# CC2530.net
KiCad netlist of a schematic drawn in Altium Designer
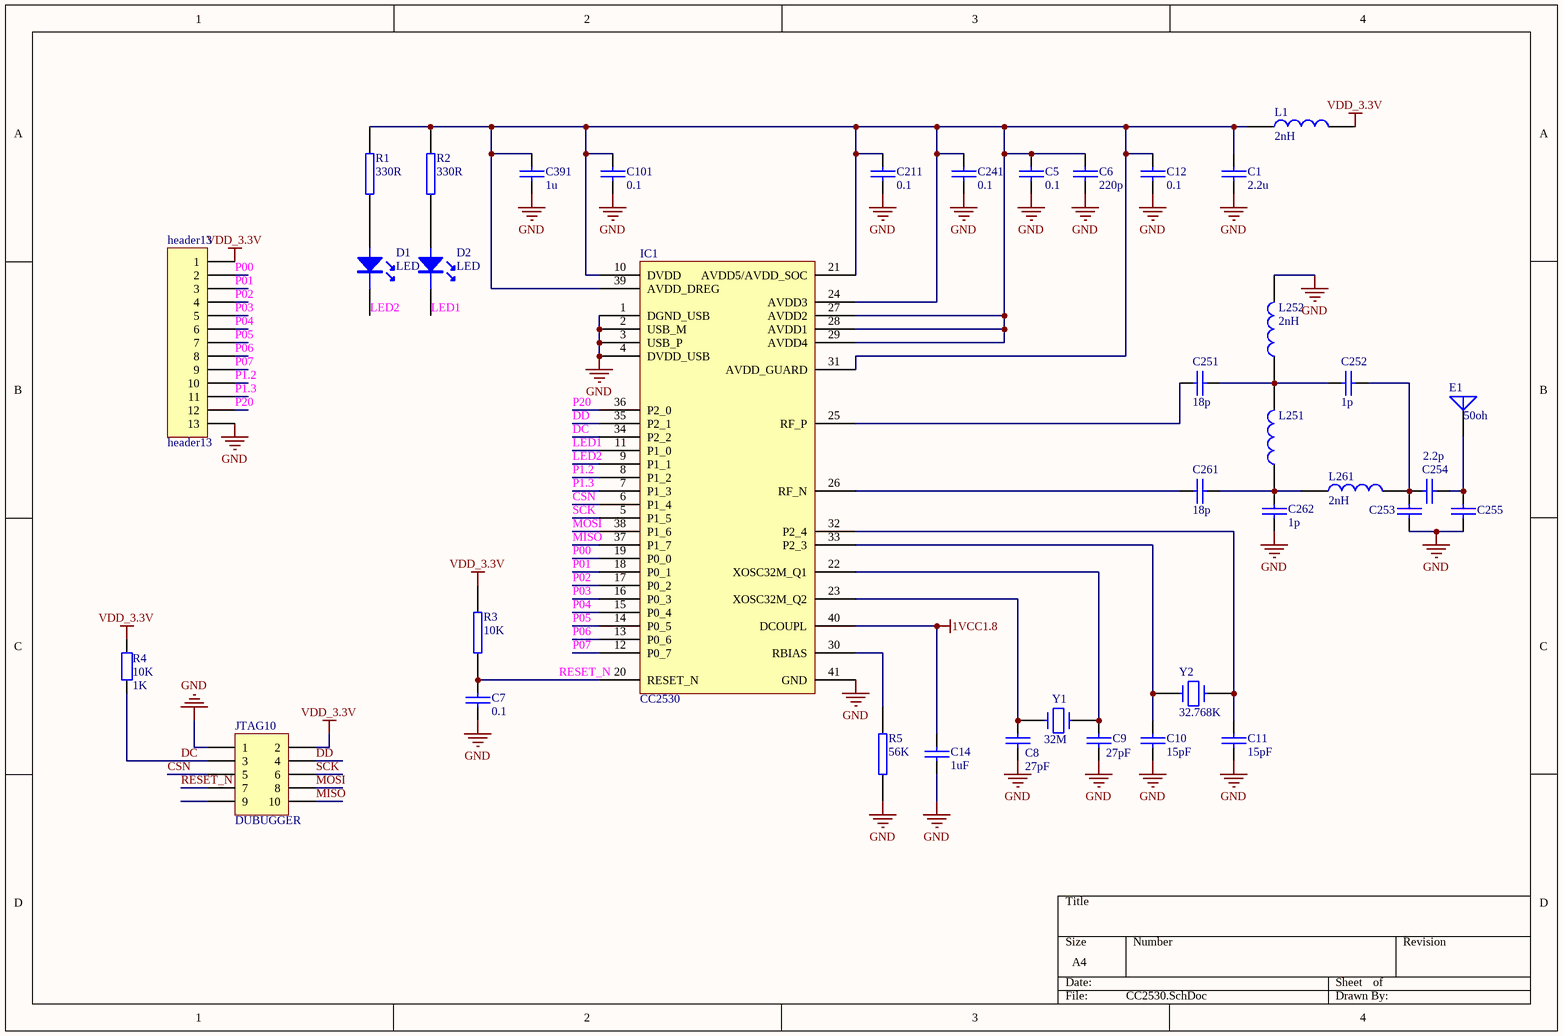
[diagram p0: CC2530.SchDoc]

(export (version "E")
  (design (tool "Eeschema 10.0.6"))
  (components
    (comp (ref "C1")
      (value "2.2u")
      (footprint "0402")
      (description "Capacitor")
      (libsource (lib "Miscellaneous Devices") (part "CAP"))
    )
    (comp (ref "C5")
      (value "0.1")
      (footprint "0402")
      (description "Capacitor")
      (libsource (lib "Miscellaneous Devices") (part "CAP"))
    )
    (comp (ref "C6")
      (value "220p")
      (footprint "0402")
      (description "Capacitor")
      (libsource (lib "Miscellaneous Devices") (part "CAP"))
    )
    (comp (ref "C7")
      (value "0.1")
      (footprint "0402")
      (description "Capacitor")
      (libsource (lib "Miscellaneous Devices") (part "CAP"))
    )
    (comp (ref "C8")
      (value "27pF")
      (footprint "0402")
      (description "Capacitor")
      (libsource (lib "Miscellaneous Devices") (part "CAP"))
    )
    (comp (ref "C9")
      (value "27pF")
      (footprint "0402")
      (description "Capacitor")
      (libsource (lib "Miscellaneous Devices") (part "CAP"))
    )
    (comp (ref "C10")
      (value "15pF")
      (footprint "0402")
      (description "Capacitor")
      (libsource (lib "Miscellaneous Devices") (part "CAP"))
    )
    (comp (ref "C11")
      (value "15pF")
      (footprint "0402")
      (description "Capacitor")
      (libsource (lib "Miscellaneous Devices") (part "CAP"))
    )
    (comp (ref "C12")
      (value "0.1")
      (footprint "0402")
      (description "Capacitor")
      (libsource (lib "Miscellaneous Devices") (part "CAP"))
    )
    (comp (ref "C14")
      (value "1uF")
      (footprint "0402")
      (description "Capacitor")
      (libsource (lib "Miscellaneous Devices") (part "CAP"))
    )
    (comp (ref "C101")
      (value "0.1")
      (footprint "0402")
      (description "Capacitor")
      (libsource (lib "Miscellaneous Devices") (part "CAP"))
    )
    (comp (ref "C211")
      (value "0.1")
      (footprint "0402")
      (description "Capacitor")
      (libsource (lib "Miscellaneous Devices") (part "CAP"))
    )
    (comp (ref "C241")
      (value "0.1")
      (footprint "0402")
      (description "Capacitor")
      (libsource (lib "Miscellaneous Devices") (part "CAP"))
    )
    (comp (ref "C251")
      (value "18p")
      (footprint "0402")
      (description "Capacitor")
      (libsource (lib "Miscellaneous Devices") (part "CAP"))
    )
    (comp (ref "C252")
      (value "1p")
      (footprint "0402")
      (description "Capacitor")
      (libsource (lib "Miscellaneous Devices") (part "CAP"))
    )
    (comp (ref "C253")
      (value "~")
      (footprint "0402")
      (description "Capacitor")
      (libsource (lib "Miscellaneous Devices") (part "CAP"))
    )
    (comp (ref "C254")
      (value "2.2p")
      (footprint "0402")
      (description "Capacitor")
      (libsource (lib "Miscellaneous Devices") (part "CAP"))
    )
    (comp (ref "C255")
      (value "~")
      (footprint "0402")
      (description "Capacitor")
      (libsource (lib "Miscellaneous Devices") (part "CAP"))
    )
    (comp (ref "C261")
      (value "18p")
      (footprint "0402")
      (description "Capacitor")
      (libsource (lib "Miscellaneous Devices") (part "CAP"))
    )
    (comp (ref "C262")
      (value "1p")
      (footprint "0402")
      (description "Capacitor")
      (libsource (lib "Miscellaneous Devices") (part "CAP"))
    )
    (comp (ref "C391")
      (value "1u")
      (footprint "0402")
      (description "Capacitor")
      (libsource (lib "Miscellaneous Devices") (part "CAP"))
    )
    (comp (ref "D1")
      (value "LED")
      (footprint "LED-0603")
      (libsource (lib "Miscellaneous Devices") (part "LED"))
    )
    (comp (ref "D2")
      (value "LED")
      (footprint "LED-0603")
      (libsource (lib "Miscellaneous Devices") (part "LED"))
    )
    (comp (ref "E1")
      (value "50oh")
      (footprint "ANT")
      (description "Generic Antenna")
      (libsource (lib "Miscellaneous Devices") (part "ANTENNA"))
    )
    (comp (ref "header13")
      (value "header13")
      (footprint "header13")
      (libsource (lib "集成库") (part "header13"))
    )
    (comp (ref "IC1") (value "CC2530") (footprint "PVQFN-N40") (libsource (lib "集成") (part "CC2530")))
    (comp (ref "JTAG10") (value "DUBUGGER") (footprint "JTAG") (libsource (lib "集成库") (part "JTAG10")))
    (comp (ref "L1")
      (value "2nH")
      (footprint "0402")
      (libsource (lib "Miscellaneous Devices") (part "INDUCTOR"))
    )
    (comp (ref "L251")
      (value "~")
      (footprint "0402")
      (libsource (lib "Miscellaneous Devices") (part "INDUCTOR"))
    )
    (comp (ref "L252")
      (value "2nH")
      (footprint "0402")
      (libsource (lib "Miscellaneous Devices") (part "INDUCTOR"))
    )
    (comp (ref "L261")
      (value "2nH")
      (footprint "0402")
      (libsource (lib "Miscellaneous Devices") (part "INDUCTOR"))
    )
    (comp (ref "R1")
      (value "330R")
      (footprint "0402")
      (libsource (lib "Miscellaneous Devices") (part "RES2"))
    )
    (comp (ref "R2")
      (value "330R")
      (footprint "0402")
      (libsource (lib "Miscellaneous Devices") (part "RES2"))
    )
    (comp (ref "R3") (value "10K") (footprint "0402") (libsource (lib "Miscellaneous Devices") (part "RES2")))
    (comp (ref "R4")
      (value "10K")
      (footprint "rea0402")
      (fields (field (name "ALTIUM_VALUE") "1K"))
      (libsource (lib "集成库") (part "res0402"))
    )
    (comp (ref "R5") (value "56K") (footprint "0402") (libsource (lib "Miscellaneous Devices") (part "RES2")))
    (comp (ref "Y1")
      (value "32M")
      (footprint "XT-SMD3225")
      (description "Crystal")
      (libsource (lib "Miscellaneous Devices") (part "CRYSTAL"))
    )
    (comp (ref "Y2")
      (value "32.768K")
      (footprint "XT_3")
      (description "Crystal")
      (libsource (lib "Miscellaneous Devices") (part "CRYSTAL"))
    )
  )
  (nets
    (net (code "1") (name "/CSN") (class "Default")
      (node (ref "IC1") (pin "6") (pinfunction "P1_4_6") (pintype "passive"))
      (node (ref "JTAG10") (pin "5") (pinfunction "5_5") (pintype "passive"))
    )
    (net (code "2") (name "/DC") (class "Default")
      (node (ref "IC1") (pin "34") (pinfunction "P2_2_34") (pintype "passive"))
      (node (ref "JTAG10") (pin "3") (pinfunction "3_3") (pintype "passive"))
      (node (ref "R4") (pin "1") (pinfunction "1_1") (pintype "passive"))
    )
    (net (code "3") (name "/DD") (class "Default")
      (node (ref "IC1") (pin "35") (pinfunction "P2_1_35") (pintype "passive"))
      (node (ref "JTAG10") (pin "4") (pinfunction "4_4") (pintype "passive"))
    )
    (net (code "4") (name "/LED1") (class "Default")
      (node (ref "D2") (pin "K") (pinfunction "2_K") (pintype "passive"))
      (node (ref "IC1") (pin "11") (pinfunction "P1_0_11") (pintype "passive"))
    )
    (net (code "5") (name "/LED2") (class "Default")
      (node (ref "D1") (pin "K") (pinfunction "2_K") (pintype "passive"))
      (node (ref "IC1") (pin "9") (pinfunction "P1_1_9") (pintype "passive"))
    )
    (net (code "6") (name "/MISO") (class "Default")
      (node (ref "IC1") (pin "37") (pinfunction "P1_7_37") (pintype "passive"))
      (node (ref "JTAG10") (pin "10") (pinfunction "10_10") (pintype "passive"))
    )
    (net (code "7") (name "/MOSI") (class "Default")
      (node (ref "IC1") (pin "38") (pinfunction "P1_6_38") (pintype "passive"))
      (node (ref "JTAG10") (pin "8") (pinfunction "8_8") (pintype "passive"))
    )
    (net (code "8") (name "/P00") (class "Default")
      (node (ref "IC1") (pin "19") (pinfunction "P0_0_19") (pintype "passive"))
      (node (ref "header13") (pin "2") (pinfunction "2_2") (pintype "passive"))
    )
    (net (code "9") (name "/P01") (class "Default")
      (node (ref "IC1") (pin "18") (pinfunction "P0_1_18") (pintype "passive"))
      (node (ref "header13") (pin "3") (pinfunction "3_3") (pintype "passive"))
    )
    (net (code "10") (name "/P1.2") (class "Default")
      (node (ref "IC1") (pin "8") (pinfunction "P1_2_8") (pintype "passive"))
      (node (ref "header13") (pin "10") (pinfunction "10_10") (pintype "passive"))
    )
    (net (code "11") (name "/P1.3") (class "Default")
      (node (ref "IC1") (pin "7") (pinfunction "P1_3_7") (pintype "passive"))
      (node (ref "header13") (pin "11") (pinfunction "11_11") (pintype "passive"))
    )
    (net (code "12") (name "/P02") (class "Default")
      (node (ref "IC1") (pin "17") (pinfunction "P0_2_17") (pintype "passive"))
      (node (ref "header13") (pin "4") (pinfunction "4_4") (pintype "passive"))
    )
    (net (code "13") (name "/P03") (class "Default")
      (node (ref "IC1") (pin "16") (pinfunction "P0_3_16") (pintype "passive"))
      (node (ref "header13") (pin "5") (pinfunction "5_5") (pintype "passive"))
    )
    (net (code "14") (name "/P04") (class "Default")
      (node (ref "IC1") (pin "15") (pinfunction "P0_4_15") (pintype "passive"))
      (node (ref "header13") (pin "6") (pinfunction "6_6") (pintype "passive"))
    )
    (net (code "15") (name "/P05") (class "Default")
      (node (ref "IC1") (pin "14") (pinfunction "P0_5_14") (pintype "passive"))
      (node (ref "header13") (pin "7") (pinfunction "7_7") (pintype "passive"))
    )
    (net (code "16") (name "/P06") (class "Default")
      (node (ref "IC1") (pin "13") (pinfunction "P0_6_13") (pintype "passive"))
      (node (ref "header13") (pin "8") (pinfunction "8_8") (pintype "passive"))
    )
    (net (code "17") (name "/P07") (class "Default")
      (node (ref "IC1") (pin "12") (pinfunction "P0_7_12") (pintype "passive"))
      (node (ref "header13") (pin "9") (pinfunction "9_9") (pintype "passive"))
    )
    (net (code "18") (name "/P20") (class "Default")
      (node (ref "IC1") (pin "36") (pinfunction "P2_0_36") (pintype "passive"))
      (node (ref "header13") (pin "12") (pinfunction "12_12") (pintype "passive"))
    )
    (net (code "19") (name "/RESET_N") (class "Default")
      (node (ref "C7") (pin "1") (pinfunction "1_1") (pintype "passive"))
      (node (ref "IC1") (pin "20") (pinfunction "RESET_N_20") (pintype "passive"))
      (node (ref "JTAG10") (pin "7") (pinfunction "7_7") (pintype "passive"))
      (node (ref "R3") (pin "1") (pinfunction "1_1") (pintype "passive"))
    )
    (net (code "20") (name "/SCK") (class "Default")
      (node (ref "IC1") (pin "5") (pinfunction "P1_5_5") (pintype "passive"))
      (node (ref "JTAG10") (pin "6") (pinfunction "6_6") (pintype "passive"))
    )
    (net (code "21") (name "1VCC1.8") (class "Default")
      (node (ref "C14") (pin "1") (pinfunction "1_1") (pintype "passive"))
      (node (ref "IC1") (pin "40") (pinfunction "DCOUPL_40") (pintype "passive"))
    )
    (net (code "22") (name "GND") (class "Default")
      (node (ref "C1") (pin "2") (pinfunction "2_2") (pintype "passive"))
      (node (ref "C10") (pin "2") (pinfunction "2_2") (pintype "passive"))
      (node (ref "C101") (pin "2") (pinfunction "2_2") (pintype "passive"))
      (node (ref "C11") (pin "2") (pinfunction "2_2") (pintype "passive"))
      (node (ref "C12") (pin "2") (pinfunction "2_2") (pintype "passive"))
      (node (ref "C14") (pin "2") (pinfunction "2_2") (pintype "passive"))
      (node (ref "C211") (pin "2") (pinfunction "2_2") (pintype "passive"))
      (node (ref "C241") (pin "2") (pinfunction "2_2") (pintype "passive"))
      (node (ref "C253") (pin "2") (pinfunction "2_2") (pintype "passive"))
      (node (ref "C255") (pin "1") (pinfunction "1_1") (pintype "passive"))
      (node (ref "C262") (pin "2") (pinfunction "2_2") (pintype "passive"))
      (node (ref "C391") (pin "2") (pinfunction "2_2") (pintype "passive"))
      (node (ref "C5") (pin "2") (pinfunction "2_2") (pintype "passive"))
      (node (ref "C6") (pin "2") (pinfunction "2_2") (pintype "passive"))
      (node (ref "C7") (pin "2") (pinfunction "2_2") (pintype "passive"))
      (node (ref "C8") (pin "2") (pinfunction "2_2") (pintype "passive"))
      (node (ref "C9") (pin "2") (pinfunction "2_2") (pintype "passive"))
      (node (ref "IC1") (pin "1") (pinfunction "DGND_USB_1") (pintype "passive"))
      (node (ref "IC1") (pin "2") (pinfunction "USB_M_2") (pintype "passive"))
      (node (ref "IC1") (pin "3") (pinfunction "USB_P_3") (pintype "passive"))
      (node (ref "IC1") (pin "4") (pinfunction "DVDD_USB_4") (pintype "passive"))
      (node (ref "IC1") (pin "41") (pinfunction "GND_41") (pintype "passive"))
      (node (ref "JTAG10") (pin "1") (pinfunction "1_1") (pintype "passive"))
      (node (ref "L252") (pin "2") (pinfunction "2_2") (pintype "passive"))
      (node (ref "R5") (pin "2") (pinfunction "2_2") (pintype "passive"))
      (node (ref "header13") (pin "13") (pinfunction "13_13") (pintype "passive"))
    )
    (net (code "23") (name "Net-(C251-Pad2)") (class "Default")
      (node (ref "C251") (pin "2") (pinfunction "2_2") (pintype "passive"))
      (node (ref "C252") (pin "1") (pinfunction "1_1") (pintype "passive"))
      (node (ref "L251") (pin "2") (pinfunction "2_2") (pintype "passive"))
      (node (ref "L252") (pin "1") (pinfunction "1_1") (pintype "passive"))
    )
    (net (code "24") (name "Net-(C252-Pad2)") (class "Default")
      (node (ref "C252") (pin "2") (pinfunction "2_2") (pintype "passive"))
      (node (ref "C253") (pin "1") (pinfunction "1_1") (pintype "passive"))
      (node (ref "C254") (pin "1") (pinfunction "1_1") (pintype "passive"))
      (node (ref "L261") (pin "2") (pinfunction "2_2") (pintype "passive"))
    )
    (net (code "25") (name "Net-(C261-Pad2)") (class "Default")
      (node (ref "C261") (pin "2") (pinfunction "2_2") (pintype "passive"))
      (node (ref "C262") (pin "1") (pinfunction "1_1") (pintype "passive"))
      (node (ref "L251") (pin "1") (pinfunction "1_1") (pintype "passive"))
      (node (ref "L261") (pin "1") (pinfunction "1_1") (pintype "passive"))
    )
    (net (code "26") (name "Net-(D1-1)") (class "Default")
      (node (ref "D1") (pin "A") (pinfunction "1_A") (pintype "passive"))
      (node (ref "R1") (pin "1") (pinfunction "1_1") (pintype "passive"))
    )
    (net (code "27") (name "Net-(D2-1)") (class "Default")
      (node (ref "D2") (pin "A") (pinfunction "1_A") (pintype "passive"))
      (node (ref "R2") (pin "1") (pinfunction "1_1") (pintype "passive"))
    )
    (net (code "28") (name "Net-(E1-A)") (class "Default")
      (node (ref "C254") (pin "2") (pinfunction "2_2") (pintype "passive"))
      (node (ref "C255") (pin "2") (pinfunction "2_2") (pintype "passive"))
      (node (ref "E1") (pin "1") (pinfunction "A_1") (pintype "passive"))
    )
    (net (code "29") (name "Net-(IC1-AVDD1)") (class "Default")
      (node (ref "C1") (pin "1") (pinfunction "1_1") (pintype "passive"))
      (node (ref "C101") (pin "1") (pinfunction "1_1") (pintype "passive"))
      (node (ref "C12") (pin "1") (pinfunction "1_1") (pintype "passive"))
      (node (ref "C211") (pin "1") (pinfunction "1_1") (pintype "passive"))
      (node (ref "C241") (pin "1") (pinfunction "1_1") (pintype "passive"))
      (node (ref "C391") (pin "1") (pinfunction "1_1") (pintype "passive"))
      (node (ref "C5") (pin "1") (pinfunction "1_1") (pintype "passive"))
      (node (ref "C6") (pin "1") (pinfunction "1_1") (pintype "passive"))
      (node (ref "IC1") (pin "10") (pinfunction "DVDD_10") (pintype "passive"))
      (node (ref "IC1") (pin "21") (pinfunction "AVDD5/AVDD_SOC_21") (pintype "passive"))
      (node (ref "IC1") (pin "24") (pinfunction "AVDD3_24") (pintype "passive"))
      (node (ref "IC1") (pin "27") (pinfunction "AVDD2_27") (pintype "passive"))
      (node (ref "IC1") (pin "28") (pinfunction "AVDD1_28") (pintype "passive"))
      (node (ref "IC1") (pin "29") (pinfunction "AVDD4_29") (pintype "passive"))
      (node (ref "IC1") (pin "31") (pinfunction "AVDD_GUARD_31") (pintype "passive"))
      (node (ref "IC1") (pin "39") (pinfunction "AVDD_DREG_39") (pintype "passive"))
      (node (ref "L1") (pin "1") (pinfunction "1_1") (pintype "passive"))
      (node (ref "R1") (pin "2") (pinfunction "2_2") (pintype "passive"))
      (node (ref "R2") (pin "2") (pinfunction "2_2") (pintype "passive"))
    )
    (net (code "30") (name "Net-(IC1-P2_3)") (class "Default")
      (node (ref "C10") (pin "1") (pinfunction "1_1") (pintype "passive"))
      (node (ref "IC1") (pin "33") (pinfunction "P2_3_33") (pintype "passive"))
      (node (ref "Y2") (pin "2") (pinfunction "2_2") (pintype "passive"))
    )
    (net (code "31") (name "Net-(IC1-P2_4)") (class "Default")
      (node (ref "C11") (pin "1") (pinfunction "1_1") (pintype "passive"))
      (node (ref "IC1") (pin "32") (pinfunction "P2_4_32") (pintype "passive"))
      (node (ref "Y2") (pin "1") (pinfunction "1_1") (pintype "passive"))
    )
    (net (code "32") (name "Net-(IC1-RBIAS)") (class "Default")
      (node (ref "IC1") (pin "30") (pinfunction "RBIAS_30") (pintype "passive"))
      (node (ref "R5") (pin "1") (pinfunction "1_1") (pintype "passive"))
    )
    (net (code "33") (name "Net-(IC1-RF_N)") (class "Default")
      (node (ref "C261") (pin "1") (pinfunction "1_1") (pintype "passive"))
      (node (ref "IC1") (pin "26") (pinfunction "RF_N_26") (pintype "passive"))
    )
    (net (code "34") (name "Net-(IC1-RF_P)") (class "Default")
      (node (ref "C251") (pin "1") (pinfunction "1_1") (pintype "passive"))
      (node (ref "IC1") (pin "25") (pinfunction "RF_P_25") (pintype "passive"))
    )
    (net (code "35") (name "Net-(IC1-XOSC32M_Q1)") (class "Default")
      (node (ref "C9") (pin "1") (pinfunction "1_1") (pintype "passive"))
      (node (ref "IC1") (pin "22") (pinfunction "XOSC32M_Q1_22") (pintype "passive"))
      (node (ref "Y1") (pin "2") (pinfunction "2_2") (pintype "passive"))
    )
    (net (code "36") (name "Net-(IC1-XOSC32M_Q2)") (class "Default")
      (node (ref "C8") (pin "1") (pinfunction "1_1") (pintype "passive"))
      (node (ref "IC1") (pin "23") (pinfunction "XOSC32M_Q2_23") (pintype "passive"))
      (node (ref "Y1") (pin "1") (pinfunction "1_1") (pintype "passive"))
    )
    (net (code "37") (name "VDD_3.3V") (class "Default")
      (node (ref "JTAG10") (pin "2") (pinfunction "2_2") (pintype "passive"))
      (node (ref "L1") (pin "2") (pinfunction "2_2") (pintype "passive"))
      (node (ref "R3") (pin "2") (pinfunction "2_2") (pintype "passive"))
      (node (ref "R4") (pin "2") (pinfunction "2_2") (pintype "passive"))
      (node (ref "header13") (pin "1") (pinfunction "1_1") (pintype "passive"))
    )
    (net (code "38") (name "unconnected-(JTAG10-Pad9)") (class "Default")
      (node (ref "JTAG10") (pin "9") (pinfunction "9_9") (pintype "passive"))
    )
  )
)
